# 3V3_PCM.net
KiCad netlist of a schematic drawn in Altium Designer
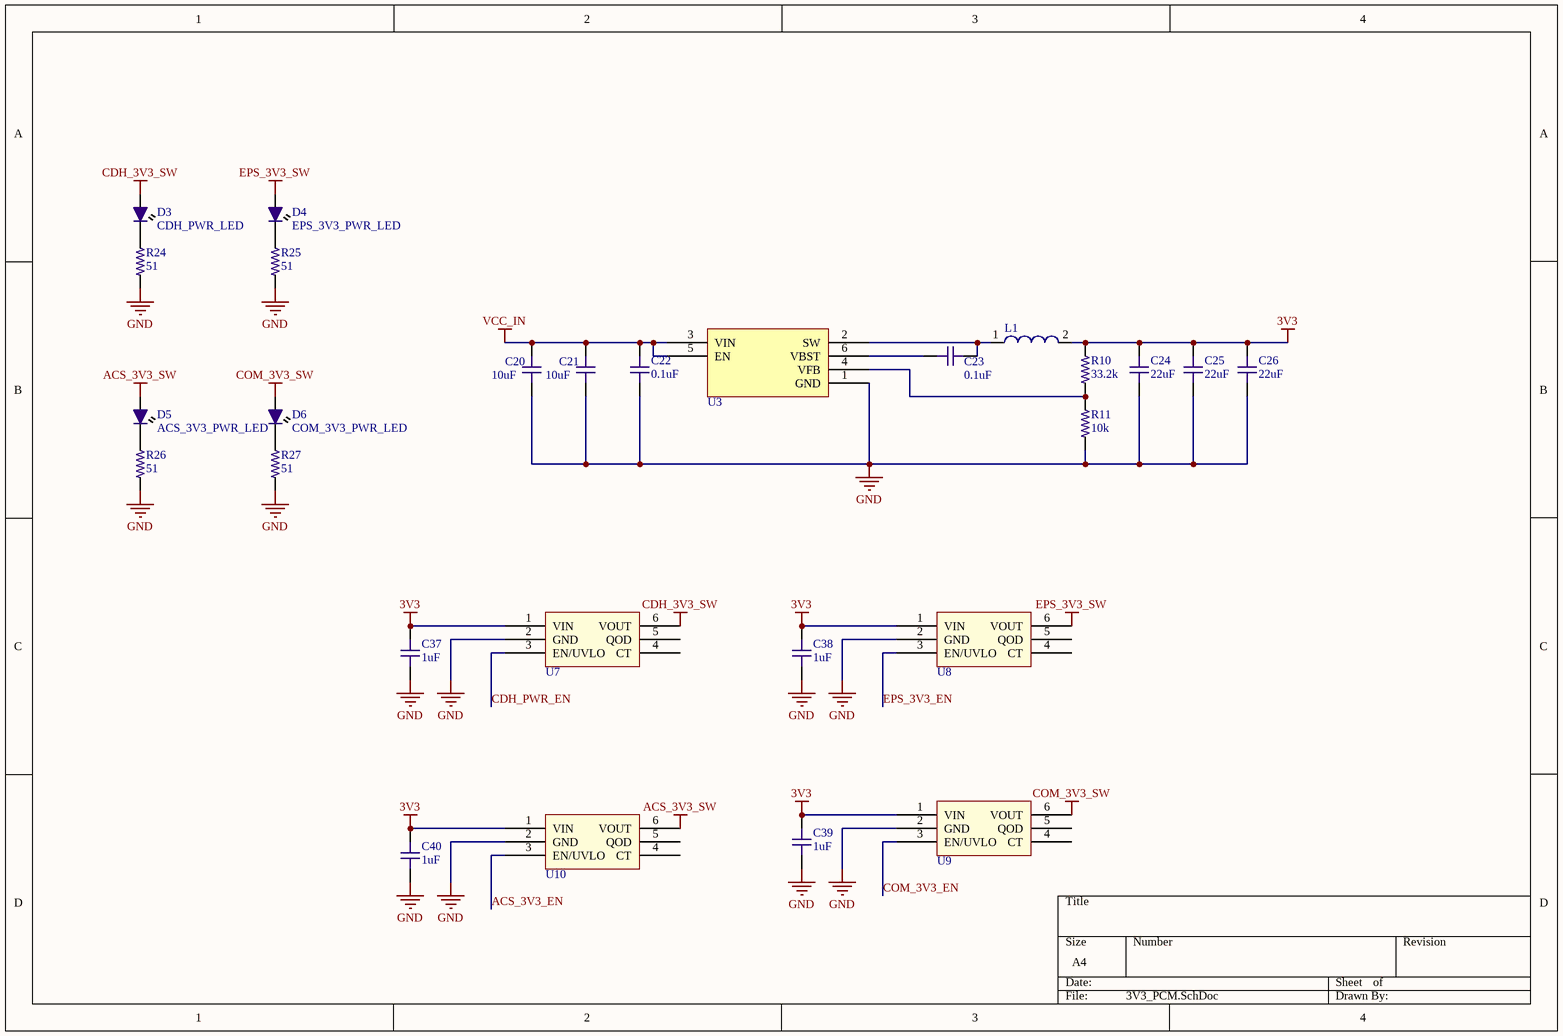
[diagram p0: 3V3_PCM.SchDoc]

(export (version "E")
  (design (tool "Eeschema 10.0.6"))
  (components
    (comp (ref "C20")
      (value "10uF")
      (footprint "C1206-IPC")
      (description "Capacitor (1206) 10uF 25V X5R 1206")
      (fields (field (name "Comment") "Cin"))
      (libsource (lib "UBC_Orbit_Shared_Components") (part "Capacitor"))
    )
    (comp (ref "C21")
      (value "10uF")
      (footprint "C1206-IPC")
      (description "Capacitor (1206) 10uF 25V X5R 1206")
      (fields (field (name "Comment") "Cin"))
      (libsource (lib "UBC_Orbit_Shared_Components") (part "Capacitor"))
    )
    (comp (ref "C22")
      (value "0.1uF")
      (footprint "C0603-IPC")
      (description "Cap Cer 0.1uF 10% 25V Cer Cap X7R 0603")
      (fields (field (name "Comment") "Cinx"))
      (libsource (lib "UBC_Orbit_Shared_Components") (part "Capacitor"))
    )
    (comp (ref "C23")
      (value "0.1uF")
      (footprint "C0603-IPC")
      (description "Cap Cer 0.1uF 10% 25V Cer Cap X7R 0603")
      (fields (field (name "Comment") "Cbst"))
      (libsource (lib "UBC_Orbit_Shared_Components") (part "Capacitor"))
    )
    (comp (ref "C24")
      (value "22uF")
      (footprint "C0603-IPC")
      (description "Cap Cer 22uF 10V X5R 0603")
      (fields (field (name "Comment") "Cout"))
      (libsource (lib "UBC_Orbit_Shared_Components") (part "Capacitor"))
    )
    (comp (ref "C25")
      (value "22uF")
      (footprint "C0603-IPC")
      (description "Cap Cer 22uF 10V X5R 0603")
      (fields (field (name "Comment") "Cout"))
      (libsource (lib "UBC_Orbit_Shared_Components") (part "Capacitor"))
    )
    (comp (ref "C26")
      (value "22uF")
      (footprint "C0603-IPC")
      (description "Cap Cer 22uF 10V X5R 0603")
      (fields (field (name "Comment") "Cout"))
      (libsource (lib "UBC_Orbit_Shared_Components") (part "Capacitor"))
    )
    (comp (ref "C37")
      (value "1uF")
      (footprint "C0603-IPC")
      (description "Capacitor (0603)")
      (fields (field (name "Comment") "Capacitor"))
      (libsource (lib "UBC_Orbit_Shared_Components") (part "Capacitor"))
    )
    (comp (ref "C38")
      (value "1uF")
      (footprint "C0603-IPC")
      (description "Capacitor (0603)")
      (fields (field (name "Comment") "Capacitor"))
      (libsource (lib "UBC_Orbit_Shared_Components") (part "Capacitor"))
    )
    (comp (ref "C39")
      (value "1uF")
      (footprint "C0603-IPC")
      (description "Capacitor (0603)")
      (fields (field (name "Comment") "Capacitor"))
      (libsource (lib "UBC_Orbit_Shared_Components") (part "Capacitor"))
    )
    (comp (ref "C40")
      (value "1uF")
      (footprint "C0603-IPC")
      (description "Capacitor (0603)")
      (fields (field (name "Comment") "Capacitor"))
      (libsource (lib "UBC_Orbit_Shared_Components") (part "Capacitor"))
    )
    (comp (ref "D3")
      (value "CDH_PWR_LED")
      (footprint "LED0603-IPC")
      (description "Red PWR_LED")
      (libsource (lib "Diodes") (part "LED 0603 SMD"))
    )
    (comp (ref "D4")
      (value "EPS_3V3_PWR_LED")
      (footprint "LED0603-IPC")
      (description "Red PWR_LED")
      (libsource (lib "Diodes") (part "LED 0603 SMD"))
    )
    (comp (ref "D5")
      (value "ACS_3V3_PWR_LED")
      (footprint "LED0603-IPC")
      (description "Red PWR_LED")
      (libsource (lib "Diodes") (part "LED 0603 SMD"))
    )
    (comp (ref "D6")
      (value "COM_3V3_PWR_LED")
      (footprint "LED0603-IPC")
      (description "Red PWR_LED")
      (libsource (lib "Diodes") (part "LED 0603 SMD"))
    )
    (comp (ref "L1")
      (value "74437349022")
      (footprint "WE-LHMI 7050")
      (description "SMD Power Inductor WE-LHMI, L=2.2 µH")
      (fields (field (name "MANUFACTURER") "Wuerth Elektronik"))
      (libsource (lib "Altium Content Vault") (part "WE-IND-INDUCTOR-2"))
    )
    (comp (ref "R10")
      (value "33.2k")
      (footprint "R0402-IPC")
      (description "33.2k 1% 0402")
      (fields (field (name "Comment") "Rfbt"))
      (libsource (lib "UBC_Orbit_Shared_Components") (part "Resistor"))
    )
    (comp (ref "R11")
      (value "10k")
      (footprint "R0402-IPC")
      (description "10k 1% 0402")
      (fields (field (name "Comment") "Rfbb"))
      (libsource (lib "UBC_Orbit_Shared_Components") (part "Resistor"))
    )
    (comp (ref "R24")
      (value "51")
      (footprint "R0603-IPC")
      (description "Chip Resistor, 0603, 51hms, 0.1W")
      (fields (field (name "Comment") "0603 Template"))
      (libsource (lib "Resistors") (part "0603 Template"))
    )
    (comp (ref "R25")
      (value "51")
      (footprint "R0603-IPC")
      (description "Chip Resistor, 0603, 51hms, 0.1W")
      (fields (field (name "Comment") "0603 Template"))
      (libsource (lib "Resistors") (part "0603 Template"))
    )
    (comp (ref "R26")
      (value "51")
      (footprint "R0603-IPC")
      (description "Chip Resistor, 0603, 51hms, 0.1W")
      (fields (field (name "Comment") "0603 Template"))
      (libsource (lib "Resistors") (part "0603 Template"))
    )
    (comp (ref "R27")
      (value "51")
      (footprint "R0603-IPC")
      (description "Chip Resistor, 0603, 51hms, 0.1W")
      (fields (field (name "Comment") "0603 Template"))
      (libsource (lib "Resistors") (part "0603 Template"))
    )
    (comp (ref "U3")
      (value "Buck")
      (footprint "Miscellaneous Devices:SOT23-6_L")
      (description "4.5V tp 17V, 5A Synchronous Step-Down Voltage Regulator")
      (libsource (lib "Integrated_Circuits") (part "TPS565208DDC"))
    )
    (comp (ref "U7")
      (value "One Channel Load Switch")
      (footprint "TPS22810-Q1")
      (description "2.7 - 18V @ 2A Max")
      (libsource (lib "Integrated_Circuits") (part "TPS22810-Q1"))
    )
    (comp (ref "U8")
      (value "One Channel Load Switch")
      (footprint "TPS22810-Q1")
      (description "2.7 - 18V @ 2A Max")
      (libsource (lib "Integrated_Circuits") (part "TPS22810-Q1"))
    )
    (comp (ref "U9")
      (value "One Channel Load Switch")
      (footprint "TPS22810-Q1")
      (description "2.7 - 18V @ 2A Max")
      (libsource (lib "Integrated_Circuits") (part "TPS22810-Q1"))
    )
    (comp (ref "U10")
      (value "One Channel Load Switch")
      (footprint "TPS22810-Q1")
      (description "2.7 - 18V @ 2A Max")
      (libsource (lib "Integrated_Circuits") (part "TPS22810-Q1"))
    )
  )
  (nets
    (net (code "1") (name "/ACS_3V3_EN") (class "Default")
      (node (ref "U10") (pin "3") (pinfunction "EN/UVLO_3") (pintype "passive"))
    )
    (net (code "2") (name "/CDH_PWR_EN") (class "Default")
      (node (ref "U7") (pin "3") (pinfunction "EN/UVLO_3") (pintype "passive"))
    )
    (net (code "3") (name "/COM_3V3_EN") (class "Default")
      (node (ref "U9") (pin "3") (pinfunction "EN/UVLO_3") (pintype "passive"))
    )
    (net (code "4") (name "/EPS_3V3_EN") (class "Default")
      (node (ref "U8") (pin "3") (pinfunction "EN/UVLO_3") (pintype "passive"))
    )
    (net (code "5") (name "3V3") (class "Default")
      (node (ref "C24") (pin "2") (pintype "passive"))
      (node (ref "C25") (pin "2") (pintype "passive"))
      (node (ref "C26") (pin "2") (pintype "passive"))
      (node (ref "C37") (pin "2") (pintype "passive"))
      (node (ref "C38") (pin "2") (pintype "passive"))
      (node (ref "C39") (pin "2") (pintype "passive"))
      (node (ref "C40") (pin "2") (pintype "passive"))
      (node (ref "L1") (pin "2") (pinfunction "2_2") (pintype "passive"))
      (node (ref "R10") (pin "2") (pintype "passive"))
      (node (ref "U10") (pin "1") (pinfunction "VIN_1") (pintype "passive"))
      (node (ref "U7") (pin "1") (pinfunction "VIN_1") (pintype "passive"))
      (node (ref "U8") (pin "1") (pinfunction "VIN_1") (pintype "passive"))
      (node (ref "U9") (pin "1") (pinfunction "VIN_1") (pintype "passive"))
    )
    (net (code "6") (name "ACS_3V3_SW") (class "Default")
      (node (ref "D5") (pin "A") (pintype "passive"))
      (node (ref "U10") (pin "6") (pinfunction "VOUT_6") (pintype "passive"))
    )
    (net (code "7") (name "CDH_3V3_SW") (class "Default")
      (node (ref "D3") (pin "A") (pintype "passive"))
      (node (ref "U7") (pin "6") (pinfunction "VOUT_6") (pintype "passive"))
    )
    (net (code "8") (name "COM_3V3_SW") (class "Default")
      (node (ref "D6") (pin "A") (pintype "passive"))
      (node (ref "U9") (pin "6") (pinfunction "VOUT_6") (pintype "passive"))
    )
    (net (code "9") (name "EPS_3V3_SW") (class "Default")
      (node (ref "D4") (pin "A") (pintype "passive"))
      (node (ref "U8") (pin "6") (pinfunction "VOUT_6") (pintype "passive"))
    )
    (net (code "10") (name "GND") (class "Default")
      (node (ref "C20") (pin "1") (pintype "passive"))
      (node (ref "C21") (pin "1") (pintype "passive"))
      (node (ref "C22") (pin "1") (pintype "passive"))
      (node (ref "C24") (pin "1") (pintype "passive"))
      (node (ref "C25") (pin "1") (pintype "passive"))
      (node (ref "C26") (pin "1") (pintype "passive"))
      (node (ref "C37") (pin "1") (pintype "passive"))
      (node (ref "C38") (pin "1") (pintype "passive"))
      (node (ref "C39") (pin "1") (pintype "passive"))
      (node (ref "C40") (pin "1") (pintype "passive"))
      (node (ref "R11") (pin "1") (pintype "passive"))
      (node (ref "R24") (pin "2") (pintype "passive"))
      (node (ref "R25") (pin "2") (pintype "passive"))
      (node (ref "R26") (pin "2") (pintype "passive"))
      (node (ref "R27") (pin "2") (pintype "passive"))
      (node (ref "U10") (pin "2") (pinfunction "GND_2") (pintype "passive"))
      (node (ref "U3") (pin "1") (pinfunction "GND_1") (pintype "passive"))
      (node (ref "U7") (pin "2") (pinfunction "GND_2") (pintype "passive"))
      (node (ref "U8") (pin "2") (pinfunction "GND_2") (pintype "passive"))
      (node (ref "U9") (pin "2") (pinfunction "GND_2") (pintype "passive"))
    )
    (net (code "11") (name "Net-(D3-PadK)") (class "Default")
      (node (ref "D3") (pin "K") (pintype "passive"))
      (node (ref "R24") (pin "1") (pintype "passive"))
    )
    (net (code "12") (name "Net-(D4-PadK)") (class "Default")
      (node (ref "D4") (pin "K") (pintype "passive"))
      (node (ref "R25") (pin "1") (pintype "passive"))
    )
    (net (code "13") (name "Net-(D5-PadK)") (class "Default")
      (node (ref "D5") (pin "K") (pintype "passive"))
      (node (ref "R26") (pin "1") (pintype "passive"))
    )
    (net (code "14") (name "Net-(D6-PadK)") (class "Default")
      (node (ref "D6") (pin "K") (pintype "passive"))
      (node (ref "R27") (pin "1") (pintype "passive"))
    )
    (net (code "15") (name "Net-(U3-SW)") (class "Default")
      (node (ref "C23") (pin "2") (pintype "passive"))
      (node (ref "L1") (pin "1") (pinfunction "1_1") (pintype "passive"))
      (node (ref "U3") (pin "2") (pinfunction "SW_2") (pintype "passive"))
    )
    (net (code "16") (name "Net-(U3-VBST)") (class "Default")
      (node (ref "C23") (pin "1") (pintype "passive"))
      (node (ref "U3") (pin "6") (pinfunction "VBST_6") (pintype "passive"))
    )
    (net (code "17") (name "Net-(U3-VFB)") (class "Default")
      (node (ref "R10") (pin "1") (pintype "passive"))
      (node (ref "R11") (pin "2") (pintype "passive"))
      (node (ref "U3") (pin "4") (pinfunction "VFB_4") (pintype "passive"))
    )
    (net (code "18") (name "VCC_IN") (class "Default")
      (node (ref "C20") (pin "2") (pintype "passive"))
      (node (ref "C21") (pin "2") (pintype "passive"))
      (node (ref "C22") (pin "2") (pintype "passive"))
      (node (ref "U3") (pin "3") (pinfunction "VIN_3") (pintype "passive"))
      (node (ref "U3") (pin "5") (pinfunction "EN_5") (pintype "passive"))
    )
    (net (code "19") (name "unconnected-(U7-CT-Pad4)") (class "Default")
      (node (ref "U7") (pin "4") (pinfunction "CT_4") (pintype "passive"))
    )
    (net (code "20") (name "unconnected-(U7-QOD-Pad5)") (class "Default")
      (node (ref "U7") (pin "5") (pinfunction "QOD_5") (pintype "passive"))
    )
    (net (code "21") (name "unconnected-(U8-CT-Pad4)") (class "Default")
      (node (ref "U8") (pin "4") (pinfunction "CT_4") (pintype "passive"))
    )
    (net (code "22") (name "unconnected-(U8-QOD-Pad5)") (class "Default")
      (node (ref "U8") (pin "5") (pinfunction "QOD_5") (pintype "passive"))
    )
    (net (code "23") (name "unconnected-(U9-CT-Pad4)") (class "Default")
      (node (ref "U9") (pin "4") (pinfunction "CT_4") (pintype "passive"))
    )
    (net (code "24") (name "unconnected-(U9-QOD-Pad5)") (class "Default")
      (node (ref "U9") (pin "5") (pinfunction "QOD_5") (pintype "passive"))
    )
    (net (code "25") (name "unconnected-(U10-CT-Pad4)") (class "Default")
      (node (ref "U10") (pin "4") (pinfunction "CT_4") (pintype "passive"))
    )
    (net (code "26") (name "unconnected-(U10-QOD-Pad5)") (class "Default")
      (node (ref "U10") (pin "5") (pinfunction "QOD_5") (pintype "passive"))
    )
  )
)
